# HuEverReset.net
KiCad netlist of a schematic drawn in EAGLE
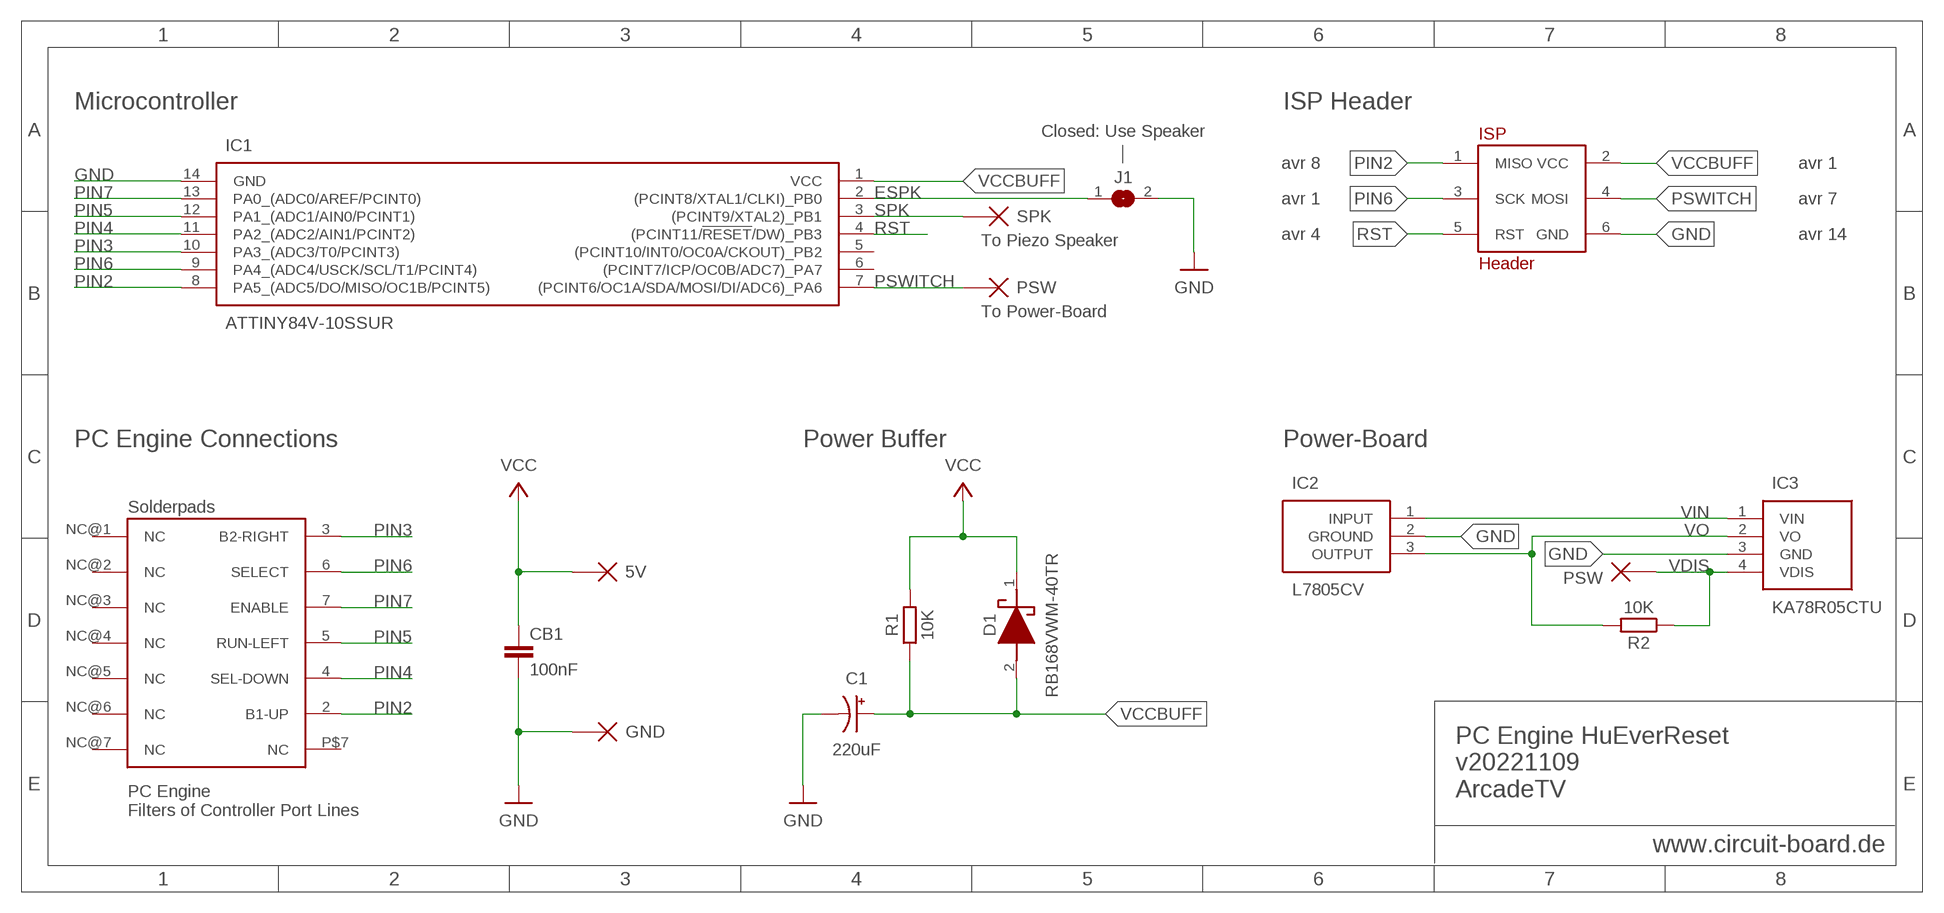
[diagram p0: schematic, sheet 1]

(export (version "E")
  (design (tool "Eeschema 10.0.6"))
  (components
    (comp (ref "C1")
      (value "220uF")
      (footprint "eagle-import:C_6032-28R")
      (libsource (lib "eagle-import") (part "CPOL-USC/6032-28R"))
    )
    (comp (ref "CB1")
      (value "100nF")
      (footprint "eagle-import:Z0805")
      (libsource (lib "eagle-import") (part "C0805"))
    )
    (comp (ref "D1")
      (value "RB168VWM-40TR")
      (footprint "eagle-import:RB168VWM40TR")
      (libsource (lib "eagle-import") (part "RB168VWM-40TR"))
    )
    (comp (ref "IC1")
      (value "ATTINY84V-10SSUR")
      (footprint "eagle-import:SOIC127P600X175-14N")
      (fields (field (name "MOUSER_PART_NUMBER") "556-ATTINY84V-10SSUR"))
      (libsource (lib "eagle-import") (part "ATTINY84V-10SSUR"))
    )
    (comp (ref "IC2")
      (value "L7805CV")
      (footprint "eagle-import:TO255P460X1020X2008-3P")
      (fields (field (name "MOUSER_PART_NUMBER") "511-L7805CV"))
      (libsource (lib "eagle-import") (part "L7805CV"))
    )
    (comp (ref "IC3")
      (value "KA78R05CTU")
      (footprint "eagle-import:PADS")
      (libsource (lib "eagle-import") (part "KA78R05CTUVERTICALMOUNT"))
    )
    (comp (ref "ISP")
      (value "Header")
      (footprint "eagle-import:TINY")
      (libsource (lib "eagle-import") (part "TINY"))
    )
    (comp (ref "J1") (value "SJ") (footprint "eagle-import:SJ") (libsource (lib "eagle-import") (part "SJ")))
    (comp (ref "P1")
      (value "5V")
      (footprint "eagle-import:PADS")
      (libsource (lib "eagle-import") (part "PAD"))
    )
    (comp (ref "P2")
      (value "GND")
      (footprint "eagle-import:PADS")
      (libsource (lib "eagle-import") (part "PAD"))
    )
    (comp (ref "P3")
      (value "PSW")
      (footprint "eagle-import:PADS")
      (libsource (lib "eagle-import") (part "PAD"))
    )
    (comp (ref "P4")
      (value "SPK")
      (footprint "eagle-import:PADS")
      (libsource (lib "eagle-import") (part "PAD"))
    )
    (comp (ref "R1")
      (value "10K")
      (footprint "eagle-import:Z0805")
      (libsource (lib "eagle-import") (part "R0805"))
    )
    (comp (ref "R2")
      (value "10K")
      (footprint "eagle-import:Z0805")
      (libsource (lib "eagle-import") (part "R0805"))
    )
    (comp (ref "U$1")
      (value "PCE-CNTRL-FILTERS")
      (footprint "eagle-import:PCE-CNTRL-FILTERS")
      (libsource (lib "eagle-import") (part "PCE-CNTRL-FILTERS"))
    )
    (comp (ref "U$2")
      (value "PSW")
      (footprint "eagle-import:PADS")
      (libsource (lib "eagle-import") (part "PAD"))
    )
  )
  (nets
    (net (code "1") (name "/ESPK") (class "Default")
      (node (ref "IC1") (pin "2") (pinfunction "(PCINT8/XTAL1/CLKI)_PB0_2") (pintype "bidirectional"))
      (node (ref "J1") (pin "1") (pinfunction "1_1") (pintype "passive"))
    )
    (net (code "2") (name "/PIN3") (class "Default")
      (node (ref "IC1") (pin "10") (pinfunction "PA3_(ADC3/T0/PCINT3)_10") (pintype "bidirectional"))
      (node (ref "U$1") (pin "3") (pinfunction "B2-RIGHT_3") (pintype "bidirectional"))
    )
    (net (code "3") (name "/PIN4") (class "Default")
      (node (ref "IC1") (pin "11") (pinfunction "PA2_(ADC2/AIN1/PCINT2)_11") (pintype "bidirectional"))
      (node (ref "U$1") (pin "4") (pinfunction "SEL-DOWN_4") (pintype "bidirectional"))
    )
    (net (code "4") (name "/PIN5") (class "Default")
      (node (ref "IC1") (pin "12") (pinfunction "PA1_(ADC1/AIN0/PCINT1)_12") (pintype "bidirectional"))
      (node (ref "U$1") (pin "5") (pinfunction "RUN-LEFT_5") (pintype "bidirectional"))
    )
    (net (code "5") (name "/PIN7") (class "Default")
      (node (ref "IC1") (pin "13") (pinfunction "PA0_(ADC0/AREF/PCINT0)_13") (pintype "bidirectional"))
      (node (ref "U$1") (pin "7") (pinfunction "ENABLE_7") (pintype "bidirectional"))
    )
    (net (code "6") (name "/SPK") (class "Default")
      (node (ref "IC1") (pin "3") (pinfunction "(PCINT9/XTAL2)_PB1_3") (pintype "bidirectional"))
      (node (ref "P4") (pin "P$1") (pinfunction "P$1_P$1") (pintype "bidirectional"))
    )
    (net (code "7") (name "/VDIS") (class "Default")
      (node (ref "IC3") (pin "4") (pinfunction "VDIS_4") (pintype "bidirectional"))
      (node (ref "R2") (pin "1") (pinfunction "1_1") (pintype "passive"))
      (node (ref "U$2") (pin "P$1") (pinfunction "P$1_P$1") (pintype "bidirectional"))
    )
    (net (code "8") (name "/VIN") (class "Default")
      (node (ref "IC2") (pin "1") (pinfunction "INPUT_1") (pintype "bidirectional"))
      (node (ref "IC3") (pin "1") (pinfunction "VIN_1") (pintype "input"))
    )
    (net (code "9") (name "/VO") (class "Default")
      (node (ref "IC2") (pin "3") (pinfunction "OUTPUT_3") (pintype "bidirectional"))
      (node (ref "IC3") (pin "2") (pinfunction "VO_2") (pintype "output"))
      (node (ref "R2") (pin "2") (pinfunction "2_2") (pintype "passive"))
    )
    (net (code "10") (name "GND") (class "Default")
      (node (ref "C1") (pin "-") (pinfunction "-_-") (pintype "passive"))
      (node (ref "CB1") (pin "2") (pinfunction "2_2") (pintype "passive"))
      (node (ref "IC1") (pin "14") (pinfunction "GND_14") (pintype "bidirectional"))
      (node (ref "IC2") (pin "2") (pinfunction "GROUND_2") (pintype "bidirectional"))
      (node (ref "IC3") (pin "3") (pinfunction "GND_3") (pintype "power_in"))
      (node (ref "ISP") (pin "6") (pinfunction "GND_6") (pintype "bidirectional"))
      (node (ref "J1") (pin "2") (pinfunction "2_2") (pintype "passive"))
      (node (ref "P2") (pin "P$1") (pinfunction "P$1_P$1") (pintype "bidirectional"))
    )
    (net (code "11") (name "PIN2") (class "Default")
      (node (ref "IC1") (pin "8") (pinfunction "PA5_(ADC5/DO/MISO/OC1B/PCINT5)_8") (pintype "bidirectional"))
      (node (ref "ISP") (pin "1") (pinfunction "MISO_1") (pintype "bidirectional"))
      (node (ref "U$1") (pin "2") (pinfunction "B1-UP_2") (pintype "bidirectional"))
    )
    (net (code "12") (name "PIN6") (class "Default")
      (node (ref "IC1") (pin "9") (pinfunction "PA4_(ADC4/USCK/SCL/T1/PCINT4)_9") (pintype "bidirectional"))
      (node (ref "ISP") (pin "3") (pinfunction "SCK_3") (pintype "bidirectional"))
      (node (ref "U$1") (pin "6") (pinfunction "SELECT_6") (pintype "bidirectional"))
    )
    (net (code "13") (name "PSWITCH") (class "Default")
      (node (ref "IC1") (pin "7") (pinfunction "(PCINT6/OC1A/SDA/MOSI/DI/ADC6)_PA6_7") (pintype "bidirectional"))
      (node (ref "ISP") (pin "4") (pinfunction "MOSI_4") (pintype "bidirectional"))
      (node (ref "P3") (pin "P$1") (pinfunction "P$1_P$1") (pintype "bidirectional"))
    )
    (net (code "14") (name "RST") (class "Default")
      (node (ref "IC1") (pin "4") (pinfunction "(PCINT11/~{RESET}/DW)_PB3_4") (pintype "bidirectional"))
      (node (ref "ISP") (pin "5") (pinfunction "RST_5") (pintype "bidirectional"))
    )
    (net (code "15") (name "VCC") (class "Default")
      (node (ref "CB1") (pin "1") (pinfunction "1_1") (pintype "passive"))
      (node (ref "D1") (pin "1") (pinfunction "K_1") (pintype "bidirectional"))
      (node (ref "P1") (pin "P$1") (pinfunction "P$1_P$1") (pintype "bidirectional"))
      (node (ref "R1") (pin "2") (pinfunction "2_2") (pintype "passive"))
    )
    (net (code "16") (name "VCCBUFF") (class "Default")
      (node (ref "C1") (pin "+") (pinfunction "+_+") (pintype "passive"))
      (node (ref "D1") (pin "2") (pinfunction "A_2") (pintype "bidirectional"))
      (node (ref "IC1") (pin "1") (pinfunction "VCC_1") (pintype "bidirectional"))
      (node (ref "ISP") (pin "2") (pinfunction "VCC_2") (pintype "bidirectional"))
      (node (ref "R1") (pin "1") (pinfunction "1_1") (pintype "passive"))
    )
    (net (code "17") (name "unconnected-(IC1-(PCINT7{slash}ICP{slash}OC0B{slash}ADC7)_PA7-Pad6)") (class "Default")
      (node (ref "IC1") (pin "6") (pinfunction "(PCINT7/ICP/OC0B/ADC7)_PA7_6") (pintype "bidirectional"))
    )
    (net (code "18") (name "unconnected-(IC1-(PCINT10{slash}INT0{slash}OC0A{slash}CKOUT)_PB2-Pad5)") (class "Default")
      (node (ref "IC1") (pin "5") (pinfunction "(PCINT10/INT0/OC0A/CKOUT)_PB2_5") (pintype "bidirectional"))
    )
    (net (code "19") (name "unconnected-(U$1-NC-PadNC@1)") (class "Default")
      (node (ref "U$1") (pin "NC@1") (pinfunction "NC_NC@1") (pintype "bidirectional"))
    )
    (net (code "20") (name "unconnected-(U$1-NC-PadNC@2)") (class "Default")
      (node (ref "U$1") (pin "NC@2") (pinfunction "NC_NC@2") (pintype "bidirectional"))
    )
    (net (code "21") (name "unconnected-(U$1-NC-PadNC@3)") (class "Default")
      (node (ref "U$1") (pin "NC@3") (pinfunction "NC_NC@3") (pintype "bidirectional"))
    )
    (net (code "22") (name "unconnected-(U$1-NC-PadNC@4)") (class "Default")
      (node (ref "U$1") (pin "NC@4") (pinfunction "NC_NC@4") (pintype "bidirectional"))
    )
    (net (code "23") (name "unconnected-(U$1-NC-PadNC@5)") (class "Default")
      (node (ref "U$1") (pin "NC@5") (pinfunction "NC_NC@5") (pintype "bidirectional"))
    )
    (net (code "24") (name "unconnected-(U$1-NC-PadNC@6)") (class "Default")
      (node (ref "U$1") (pin "NC@6") (pinfunction "NC_NC@6") (pintype "bidirectional"))
    )
    (net (code "25") (name "unconnected-(U$1-NC-PadNC@7)") (class "Default")
      (node (ref "U$1") (pin "NC@7") (pinfunction "NC_NC@7") (pintype "bidirectional"))
    )
    (net (code "26") (name "unconnected-(U$1-NC-PadP$7)") (class "Default")
      (node (ref "U$1") (pin "P$7") (pinfunction "NC_P$7") (pintype "bidirectional"))
    )
  )
)
